# Dosringspumpestyring.net
KiCad netlist of a schematic drawn in EAGLE
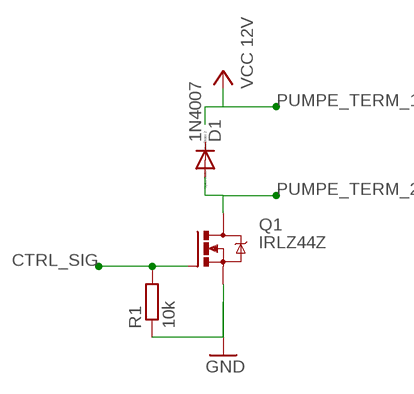
[diagram p0: schematic, sheet 1]

(export (version "E")
  (design (tool "Eeschema 10.0.6"))
  (components
    (comp (ref "D1")
      (value "1N4007")
      (footprint "eagle-import:DO41-10")
      (libsource (lib "eagle-import") (part "1N4004"))
    )
    (comp (ref "Q1")
      (value "IRLZ44Z")
      (footprint "eagle-import:TO220BH")
      (libsource (lib "eagle-import") (part "IRLZ44Z"))
    )
    (comp (ref "R1")
      (value "10k")
      (footprint "eagle-import:0204V")
      (libsource (lib "eagle-import") (part "R-EU_0204/2V"))
    )
  )
  (nets
    (net (code "1") (name "/CTRL_SIG") (class "Default")
      (node (ref "Q1") (pin "G") (pinfunction "G_G") (pintype "passive"))
      (node (ref "R1") (pin "2") (pinfunction "2_2") (pintype "passive"))
    )
    (net (code "2") (name "/PUMPE_TERM_2") (class "Default")
      (node (ref "D1") (pin "A") (pinfunction "A_A") (pintype "passive"))
      (node (ref "Q1") (pin "D") (pinfunction "D_D") (pintype "passive"))
    )
    (net (code "3") (name "GND") (class "Default")
      (node (ref "Q1") (pin "S") (pinfunction "S_S") (pintype "passive"))
      (node (ref "R1") (pin "1") (pinfunction "1_1") (pintype "passive"))
    )
    (net (code "5") (name "unconnected-(D1-PadC)") (class "Default")
      (node (ref "D1") (pin "C") (pinfunction "C_C") (pintype "passive"))
    )
  )
)
